# karmanDB_pyro.net
KiCad netlist of a schematic drawn in Altium Designer
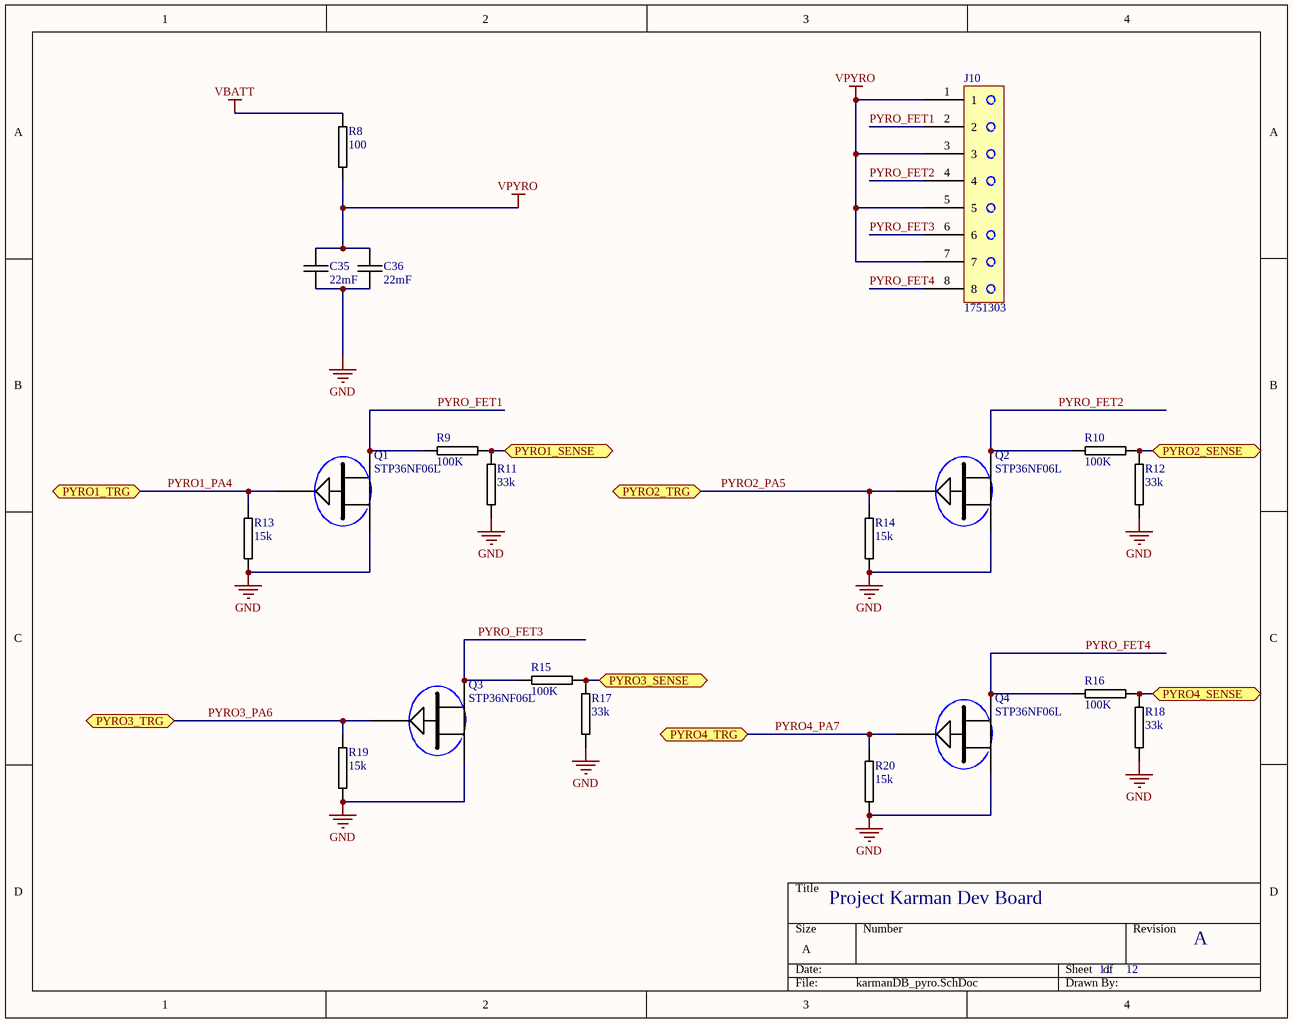
[diagram p0: karmanDB_pyro.SchDoc]

(export (version "E")
  (design (tool "Eeschema 10.0.6"))
  (components
    (comp (ref "C35")
      (value "22mF")
      (footprint "AVX_BZ01")
      (description "CAP 22MF -20% +80% 12V SMD")
      (fields
        (field (name "MANUFACTURER") "AVX Corporation")
        (field (name "MANUFACTURER PART NUMBER") "BZ01CA223ZSB")
      )
      (libsource (lib "karman_pcb") (part "BZ01CA223ZSB"))
    )
    (comp (ref "C36")
      (value "22mF")
      (footprint "AVX_BZ01")
      (description "CAP 22MF -20% +80% 12V SMD")
      (fields
        (field (name "MANUFACTURER") "AVX Corporation")
        (field (name "MANUFACTURER PART NUMBER") "BZ01CA223ZSB")
      )
      (libsource (lib "karman_pcb") (part "BZ01CA223ZSB"))
    )
    (comp (ref "J10")
      (value "1751303")
      (footprint "1751303")
      (description "CONN TERM BLOCK 8POS 3.5MM")
      (fields (field (name "MANUFACTURER") "Phoenix Contact") (field (name "VOLTAGE") "300V"))
      (libsource (lib "karman_pcb") (part "1751303"))
    )
    (comp (ref "Q1")
      (value "STP36NF06L")
      (footprint "ST(P/B)36NF06L")
      (description "MOSFET N-CH 60V 30A TO-220")
      (fields (field (name "MANUFACTURER") "STMicroelectronics"))
      (libsource (lib "karman_pcb") (part "STP36NF06L"))
    )
    (comp (ref "Q2")
      (value "STP36NF06L")
      (footprint "ST(P/B)36NF06L")
      (description "MOSFET N-CH 60V 30A TO-220")
      (fields (field (name "MANUFACTURER") "STMicroelectronics"))
      (libsource (lib "karman_pcb") (part "STP36NF06L"))
    )
    (comp (ref "Q3")
      (value "STP36NF06L")
      (footprint "ST(P/B)36NF06L")
      (description "MOSFET N-CH 60V 30A TO-220")
      (fields (field (name "MANUFACTURER") "STMicroelectronics"))
      (libsource (lib "karman_pcb") (part "STP36NF06L"))
    )
    (comp (ref "Q4")
      (value "STP36NF06L")
      (footprint "ST(P/B)36NF06L")
      (description "MOSFET N-CH 60V 30A TO-220")
      (fields (field (name "MANUFACTURER") "STMicroelectronics"))
      (libsource (lib "karman_pcb") (part "STP36NF06L"))
    )
    (comp (ref "R8")
      (value "100")
      (footprint "PANASONIC_ERJ1T")
      (description "RES SMD 100 OHM 5% 1W 2512")
      (libsource (lib "project_symbols") (part "RES_PANASONIC_ERJ-1TYJ101U"))
    )
    (comp (ref "R9")
      (value "100K")
      (footprint "PANASONIC_ERJ3R")
      (description "RES SMD 100K OHM 5% 1/10W 0603")
      (fields
        (field (name "MANUFACTURER") "Panasonic Electronic Components")
        (field (name "MANUFACTURER PART NUMBER") "ERJ-3GEYJ104V")
      )
      (libsource (lib "project_symbols") (part "RES_PANASONIC_ERJ-3GEYJ104V"))
    )
    (comp (ref "R10")
      (value "100K")
      (footprint "PANASONIC_ERJ3R")
      (description "RES SMD 100K OHM 5% 1/10W 0603")
      (fields
        (field (name "MANUFACTURER") "Panasonic Electronic Components")
        (field (name "MANUFACTURER PART NUMBER") "ERJ-3GEYJ104V")
      )
      (libsource (lib "project_symbols") (part "RES_PANASONIC_ERJ-3GEYJ104V"))
    )
    (comp (ref "R11")
      (value "33k")
      (footprint "PANASONIC_ERJ2R_SERIES")
      (description "RES SMD 33K OHM 5% 1/10W 0402")
      (fields
        (field (name "MANUFACTURER") "Panasonic Electronic Components")
        (field (name "MANUFACTURER PART NUMBER") "ERJ-2GEJ333X")
      )
      (libsource (lib "project_symbols") (part "RES_PANASONIC_ERJ-2GEJ333X"))
    )
    (comp (ref "R12")
      (value "33k")
      (footprint "PANASONIC_ERJ2R_SERIES")
      (description "RES SMD 33K OHM 5% 1/10W 0402")
      (fields
        (field (name "MANUFACTURER") "Panasonic Electronic Components")
        (field (name "MANUFACTURER PART NUMBER") "ERJ-2GEJ333X")
      )
      (libsource (lib "project_symbols") (part "RES_PANASONIC_ERJ-2GEJ333X"))
    )
    (comp (ref "R13")
      (value "15k")
      (footprint "PANASONIC_ERJ3R")
      (description "RES SMD 15K OHM 0.5% 1/10W 0603")
      (fields
        (field (name "MANUFACTURER") "Panasonic Electronic Components")
        (field (name "MANUFACTURER PART NUMBER") "ERA-3AED153V")
      )
      (libsource (lib "project_symbols") (part "RES_PAN_ERA-3AED153V"))
    )
    (comp (ref "R14")
      (value "15k")
      (footprint "PANASONIC_ERJ3R")
      (description "RES SMD 15K OHM 0.5% 1/10W 0603")
      (fields
        (field (name "MANUFACTURER") "Panasonic Electronic Components")
        (field (name "MANUFACTURER PART NUMBER") "ERA-3AED153V")
      )
      (libsource (lib "project_symbols") (part "RES_PAN_ERA-3AED153V"))
    )
    (comp (ref "R15")
      (value "100K")
      (footprint "PANASONIC_ERJ3R")
      (description "RES SMD 100K OHM 5% 1/10W 0603")
      (fields
        (field (name "MANUFACTURER") "Panasonic Electronic Components")
        (field (name "MANUFACTURER PART NUMBER") "ERJ-3GEYJ104V")
      )
      (libsource (lib "project_symbols") (part "RES_PANASONIC_ERJ-3GEYJ104V"))
    )
    (comp (ref "R16")
      (value "100K")
      (footprint "PANASONIC_ERJ3R")
      (description "RES SMD 100K OHM 5% 1/10W 0603")
      (fields
        (field (name "MANUFACTURER") "Panasonic Electronic Components")
        (field (name "MANUFACTURER PART NUMBER") "ERJ-3GEYJ104V")
      )
      (libsource (lib "project_symbols") (part "RES_PANASONIC_ERJ-3GEYJ104V"))
    )
    (comp (ref "R17")
      (value "33k")
      (footprint "PANASONIC_ERJ2R_SERIES")
      (description "RES SMD 33K OHM 5% 1/10W 0402")
      (fields
        (field (name "MANUFACTURER") "Panasonic Electronic Components")
        (field (name "MANUFACTURER PART NUMBER") "ERJ-2GEJ333X")
      )
      (libsource (lib "project_symbols") (part "RES_PANASONIC_ERJ-2GEJ333X"))
    )
    (comp (ref "R18")
      (value "33k")
      (footprint "PANASONIC_ERJ2R_SERIES")
      (description "RES SMD 33K OHM 5% 1/10W 0402")
      (fields
        (field (name "MANUFACTURER") "Panasonic Electronic Components")
        (field (name "MANUFACTURER PART NUMBER") "ERJ-2GEJ333X")
      )
      (libsource (lib "project_symbols") (part "RES_PANASONIC_ERJ-2GEJ333X"))
    )
    (comp (ref "R19")
      (value "15k")
      (footprint "PANASONIC_ERJ3R")
      (description "RES SMD 15K OHM 0.5% 1/10W 0603")
      (fields
        (field (name "MANUFACTURER") "Panasonic Electronic Components")
        (field (name "MANUFACTURER PART NUMBER") "ERA-3AED153V")
      )
      (libsource (lib "project_symbols") (part "RES_PAN_ERA-3AED153V"))
    )
    (comp (ref "R20")
      (value "15k")
      (footprint "PANASONIC_ERJ3R")
      (description "RES SMD 15K OHM 0.5% 1/10W 0603")
      (fields
        (field (name "MANUFACTURER") "Panasonic Electronic Components")
        (field (name "MANUFACTURER PART NUMBER") "ERA-3AED153V")
      )
      (libsource (lib "project_symbols") (part "RES_PAN_ERA-3AED153V"))
    )
  )
  (nets
    (net (code "1") (name "/PYRO1_PA4") (class "Default")
      (node (ref "Q1") (pin "1") (pinfunction "G_1") (pintype "passive"))
      (node (ref "R13") (pin "1") (pintype "passive"))
    )
    (net (code "2") (name "/PYRO1_SENSE") (class "Default")
      (node (ref "R11") (pin "1") (pintype "passive"))
      (node (ref "R9") (pin "2") (pintype "passive"))
    )
    (net (code "3") (name "/PYRO2_PA5") (class "Default")
      (node (ref "Q2") (pin "1") (pinfunction "G_1") (pintype "passive"))
      (node (ref "R14") (pin "1") (pintype "passive"))
    )
    (net (code "4") (name "/PYRO2_SENSE") (class "Default")
      (node (ref "R10") (pin "2") (pintype "passive"))
      (node (ref "R12") (pin "1") (pintype "passive"))
    )
    (net (code "5") (name "/PYRO3_PA6") (class "Default")
      (node (ref "Q3") (pin "1") (pinfunction "G_1") (pintype "passive"))
      (node (ref "R19") (pin "1") (pintype "passive"))
    )
    (net (code "6") (name "/PYRO3_SENSE") (class "Default")
      (node (ref "R15") (pin "2") (pintype "passive"))
      (node (ref "R17") (pin "1") (pintype "passive"))
    )
    (net (code "7") (name "/PYRO4_PA7") (class "Default")
      (node (ref "Q4") (pin "1") (pinfunction "G_1") (pintype "passive"))
      (node (ref "R20") (pin "1") (pintype "passive"))
    )
    (net (code "8") (name "/PYRO4_SENSE") (class "Default")
      (node (ref "R16") (pin "2") (pintype "passive"))
      (node (ref "R18") (pin "1") (pintype "passive"))
    )
    (net (code "9") (name "/PYRO_FET1") (class "Default")
      (node (ref "J10") (pin "2") (pinfunction "2_2") (pintype "passive"))
      (node (ref "Q1") (pin "2") (pinfunction "D_2") (pintype "passive"))
      (node (ref "R9") (pin "1") (pintype "passive"))
    )
    (net (code "10") (name "/PYRO_FET2") (class "Default")
      (node (ref "J10") (pin "4") (pinfunction "4_4") (pintype "passive"))
      (node (ref "Q2") (pin "2") (pinfunction "D_2") (pintype "passive"))
      (node (ref "R10") (pin "1") (pintype "passive"))
    )
    (net (code "11") (name "/PYRO_FET3") (class "Default")
      (node (ref "J10") (pin "6") (pinfunction "6_6") (pintype "passive"))
      (node (ref "Q3") (pin "2") (pinfunction "D_2") (pintype "passive"))
      (node (ref "R15") (pin "1") (pintype "passive"))
    )
    (net (code "12") (name "/PYRO_FET4") (class "Default")
      (node (ref "J10") (pin "8") (pinfunction "8_8") (pintype "passive"))
      (node (ref "Q4") (pin "2") (pinfunction "D_2") (pintype "passive"))
      (node (ref "R16") (pin "1") (pintype "passive"))
    )
    (net (code "13") (name "GND") (class "Default")
      (node (ref "C35") (pin "2") (pintype "passive"))
      (node (ref "C36") (pin "2") (pintype "passive"))
      (node (ref "Q1") (pin "3") (pinfunction "S_3") (pintype "passive"))
      (node (ref "Q2") (pin "3") (pinfunction "S_3") (pintype "passive"))
      (node (ref "Q3") (pin "3") (pinfunction "S_3") (pintype "passive"))
      (node (ref "Q4") (pin "3") (pinfunction "S_3") (pintype "passive"))
      (node (ref "R11") (pin "2") (pintype "passive"))
      (node (ref "R12") (pin "2") (pintype "passive"))
      (node (ref "R13") (pin "2") (pintype "passive"))
      (node (ref "R14") (pin "2") (pintype "passive"))
      (node (ref "R17") (pin "2") (pintype "passive"))
      (node (ref "R18") (pin "2") (pintype "passive"))
      (node (ref "R19") (pin "2") (pintype "passive"))
      (node (ref "R20") (pin "2") (pintype "passive"))
    )
    (net (code "14") (name "VBATT") (class "Default") (node (ref "R8") (pin "1") (pintype "passive")))
    (net (code "15") (name "VPYRO") (class "Default")
      (node (ref "C35") (pin "1") (pintype "passive"))
      (node (ref "C36") (pin "1") (pintype "passive"))
      (node (ref "J10") (pin "1") (pinfunction "1_1") (pintype "passive"))
      (node (ref "J10") (pin "3") (pinfunction "3_3") (pintype "passive"))
      (node (ref "J10") (pin "5") (pinfunction "5_5") (pintype "passive"))
      (node (ref "J10") (pin "7") (pinfunction "7_7") (pintype "passive"))
      (node (ref "R8") (pin "2") (pintype "passive"))
    )
  )
)
